# Connectors.net
KiCad netlist of a schematic drawn in Altium Designer
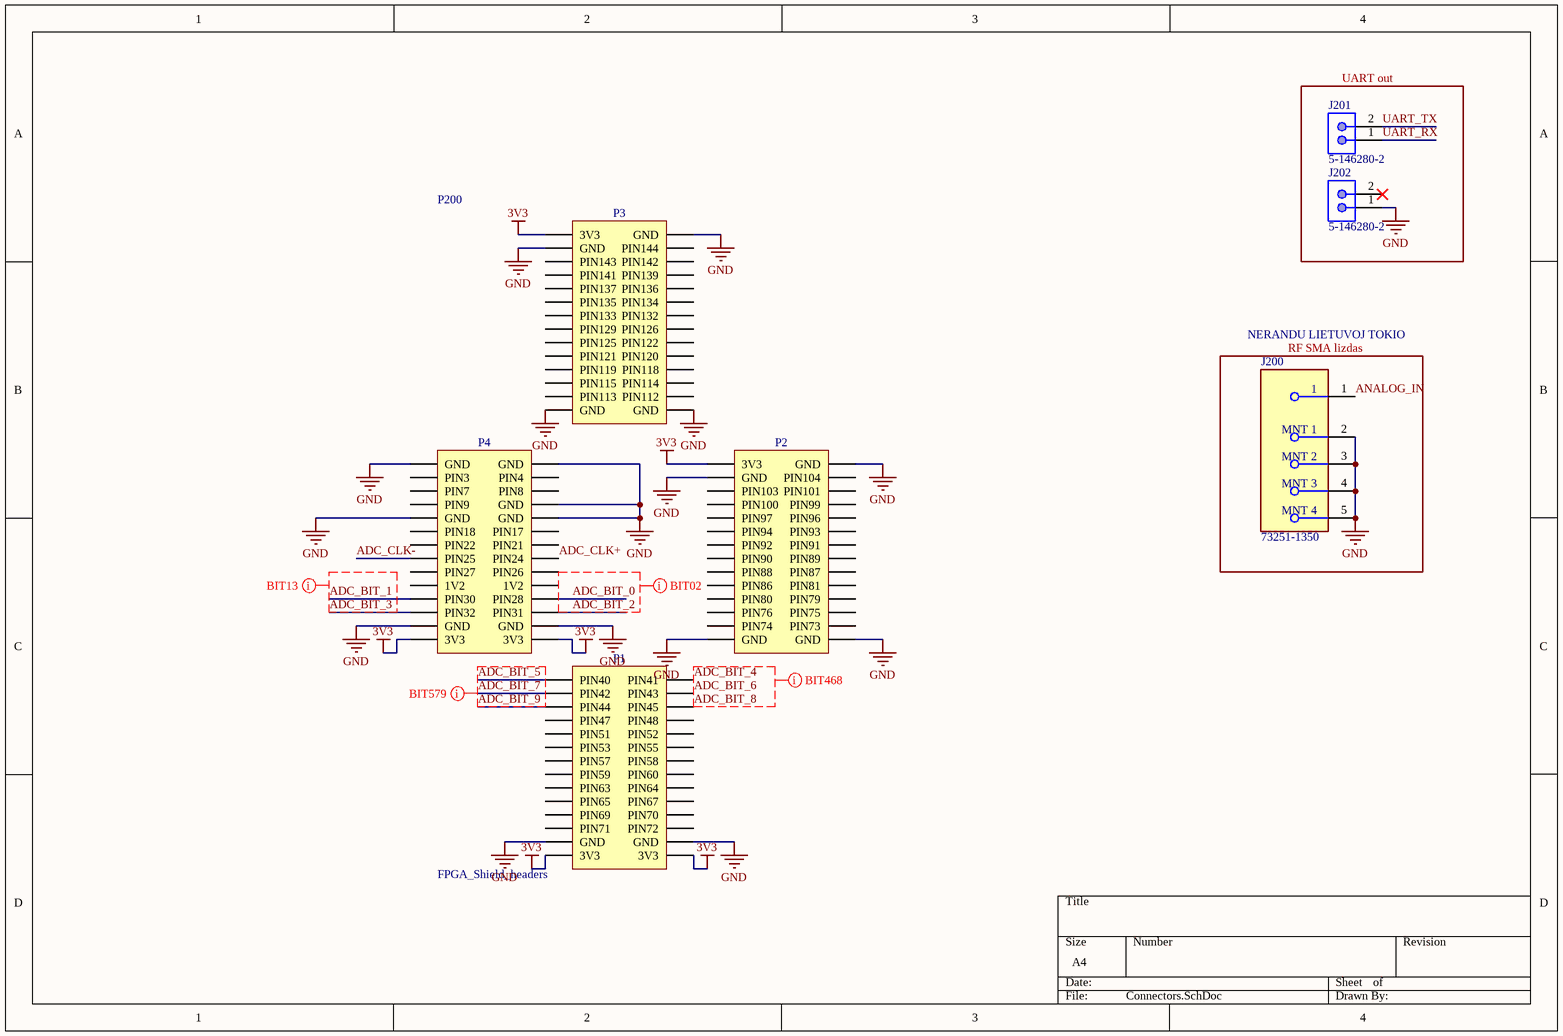
[diagram p0: Connectors.SchDoc]

(export (version "E")
  (design (tool "Eeschema 10.0.6"))
  (components
    (comp (ref "J200")
      (value "73251-1350")
      (footprint "FP-73251-1350-MFG")
      (description "CONN SMA JACK STR 50 OHM SMD")
      (fields
        (field (name "OCTOPART") "https://octopart.com/73251-1350-molex-5414390")
        (field (name "MANUFACTURER") "Molex")
      )
      (libsource (lib "Altium Content Vault") (part "474d33b8a96b1ade9ed6dd87a2b06d4"))
    )
    (comp (ref "J201")
      (value "5-146280-2")
      (footprint "TECO-5-146280-2_V")
      (fields (field (name "MANUFACTURER") "TE Connectivity"))
      (libsource (lib "Altium Content Vault") (part "CN-1P-M-R2"))
    )
    (comp (ref "J202")
      (value "5-146280-2")
      (footprint "TECO-5-146280-2_V")
      (fields (field (name "MANUFACTURER") "TE Connectivity"))
      (libsource (lib "Altium Content Vault") (part "CN-1P-M-R2"))
    )
    (comp (ref "P200")
      (value "FPGA_Shield_headers")
      (footprint "FPGA_SHIELD_HEADER_FOOTPRINT")
      (libsource (lib "Schlib1") (part "FPGA_Shield_headers"))
    )
  )
  (nets
    (net (code "1") (name "/ADC_BIT_0") (class "Default")
      (node (ref "P200") (pin "22") (pinfunction "PIN28_22") (pintype "passive"))
    )
    (net (code "2") (name "/ADC_BIT_1") (class "Default")
      (node (ref "P200") (pin "21") (pinfunction "PIN30_21") (pintype "passive"))
    )
    (net (code "3") (name "/ADC_BIT_2") (class "Default")
      (node (ref "P200") (pin "24") (pinfunction "PIN31_24") (pintype "passive"))
    )
    (net (code "4") (name "/ADC_BIT_3") (class "Default")
      (node (ref "P200") (pin "23") (pinfunction "PIN32_23") (pintype "passive"))
    )
    (net (code "5") (name "/ADC_BIT_4") (class "Default")
      (node (ref "P200") (pin "86") (pinfunction "PIN41_86") (pintype "passive"))
    )
    (net (code "6") (name "/ADC_BIT_5") (class "Default")
      (node (ref "P200") (pin "85") (pinfunction "PIN40_85") (pintype "passive"))
    )
    (net (code "7") (name "/ADC_BIT_6") (class "Default")
      (node (ref "P200") (pin "88") (pinfunction "PIN43_88") (pintype "passive"))
    )
    (net (code "8") (name "/ADC_BIT_7") (class "Default")
      (node (ref "P200") (pin "87") (pinfunction "PIN42_87") (pintype "passive"))
    )
    (net (code "9") (name "/ADC_BIT_8") (class "Default")
      (node (ref "P200") (pin "90") (pinfunction "PIN45_90") (pintype "passive"))
    )
    (net (code "10") (name "/ADC_BIT_9") (class "Default")
      (node (ref "P200") (pin "89") (pinfunction "PIN44_89") (pintype "passive"))
    )
    (net (code "11") (name "/ADC_CLK+") (class "Default")
      (node (ref "P200") (pin "16") (pinfunction "PIN24_16") (pintype "passive"))
    )
    (net (code "12") (name "/ADC_CLK-") (class "Default")
      (node (ref "P200") (pin "15") (pinfunction "PIN25_15") (pintype "passive"))
    )
    (net (code "13") (name "/ANALOG_IN") (class "Default")
      (node (ref "J200") (pin "1") (pinfunction "1_1") (pintype "passive"))
    )
    (net (code "14") (name "/UART_RX") (class "Default")
      (node (ref "J201") (pin "1") (pinfunction "1_1") (pintype "passive"))
    )
    (net (code "15") (name "/UART_TX") (class "Default")
      (node (ref "J201") (pin "2") (pinfunction "2_2") (pintype "passive"))
    )
    (net (code "16") (name "3V3") (class "Default")
      (node (ref "P200") (pin "111") (pinfunction "3V3_111") (pintype "passive"))
      (node (ref "P200") (pin "112") (pinfunction "3V3_112") (pintype "passive"))
      (node (ref "P200") (pin "27") (pinfunction "3V3_27") (pintype "passive"))
      (node (ref "P200") (pin "28") (pinfunction "3V3_28") (pintype "passive"))
      (node (ref "P200") (pin "29") (pinfunction "3V3_29") (pintype "passive"))
      (node (ref "P200") (pin "57") (pinfunction "3V3_57") (pintype "passive"))
    )
    (net (code "17") (name "GND") (class "Default")
      (node (ref "J200") (pin "2") (pinfunction "MNT_1_2") (pintype "passive"))
      (node (ref "J200") (pin "3") (pinfunction "MNT_2_3") (pintype "passive"))
      (node (ref "J200") (pin "4") (pinfunction "MNT_3_4") (pintype "passive"))
      (node (ref "J200") (pin "5") (pinfunction "MNT_4_5") (pintype "passive"))
      (node (ref "J202") (pin "1") (pinfunction "1_1") (pintype "passive"))
      (node (ref "P200") (pin "1") (pinfunction "GND_1") (pintype "passive"))
      (node (ref "P200") (pin "10") (pinfunction "GND_10") (pintype "passive"))
      (node (ref "P200") (pin "109") (pinfunction "GND_109") (pintype "passive"))
      (node (ref "P200") (pin "110") (pinfunction "GND_110") (pintype "passive"))
      (node (ref "P200") (pin "2") (pinfunction "GND_2") (pintype "passive"))
      (node (ref "P200") (pin "25") (pinfunction "GND_25") (pintype "passive"))
      (node (ref "P200") (pin "26") (pinfunction "GND_26") (pintype "passive"))
      (node (ref "P200") (pin "30") (pinfunction "GND_30") (pintype "passive"))
      (node (ref "P200") (pin "31") (pinfunction "GND_31") (pintype "passive"))
      (node (ref "P200") (pin "55") (pinfunction "GND_55") (pintype "passive"))
      (node (ref "P200") (pin "56") (pinfunction "GND_56") (pintype "passive"))
      (node (ref "P200") (pin "58") (pinfunction "GND_58") (pintype "passive"))
      (node (ref "P200") (pin "59") (pinfunction "GND_59") (pintype "passive"))
      (node (ref "P200") (pin "8") (pinfunction "GND_8") (pintype "passive"))
      (node (ref "P200") (pin "83") (pinfunction "GND_83") (pintype "passive"))
      (node (ref "P200") (pin "84") (pinfunction "GND_84") (pintype "passive"))
      (node (ref "P200") (pin "9") (pinfunction "GND_9") (pintype "passive"))
    )
    (net (code "18") (name "unconnected-(J202-Pad2)") (class "Default")
      (node (ref "J202") (pin "2") (pinfunction "2_2") (pintype "passive+no_connect"))
    )
    (net (code "19") (name "unconnected-(P200-1V2-Pad19)") (class "Default")
      (node (ref "P200") (pin "19") (pinfunction "1V2_19") (pintype "passive"))
    )
    (net (code "20") (name "unconnected-(P200-1V2-Pad20)") (class "Default")
      (node (ref "P200") (pin "20") (pinfunction "1V2_20") (pintype "passive"))
    )
    (net (code "21") (name "unconnected-(P200-PIN3-Pad3)") (class "Default")
      (node (ref "P200") (pin "3") (pinfunction "PIN3_3") (pintype "passive"))
    )
    (net (code "22") (name "unconnected-(P200-PIN4-Pad4)") (class "Default")
      (node (ref "P200") (pin "4") (pinfunction "PIN4_4") (pintype "passive"))
    )
    (net (code "23") (name "unconnected-(P200-PIN7-Pad5)") (class "Default")
      (node (ref "P200") (pin "5") (pinfunction "PIN7_5") (pintype "passive"))
    )
    (net (code "24") (name "unconnected-(P200-PIN8-Pad6)") (class "Default")
      (node (ref "P200") (pin "6") (pinfunction "PIN8_6") (pintype "passive"))
    )
    (net (code "25") (name "unconnected-(P200-PIN9-Pad7)") (class "Default")
      (node (ref "P200") (pin "7") (pinfunction "PIN9_7") (pintype "passive"))
    )
    (net (code "26") (name "unconnected-(P200-PIN17-Pad12)") (class "Default")
      (node (ref "P200") (pin "12") (pinfunction "PIN17_12") (pintype "passive"))
    )
    (net (code "27") (name "unconnected-(P200-PIN18-Pad11)") (class "Default")
      (node (ref "P200") (pin "11") (pinfunction "PIN18_11") (pintype "passive"))
    )
    (net (code "28") (name "unconnected-(P200-PIN21-Pad14)") (class "Default")
      (node (ref "P200") (pin "14") (pinfunction "PIN21_14") (pintype "passive"))
    )
    (net (code "29") (name "unconnected-(P200-PIN22-Pad13)") (class "Default")
      (node (ref "P200") (pin "13") (pinfunction "PIN22_13") (pintype "passive"))
    )
    (net (code "30") (name "unconnected-(P200-PIN26-Pad18)") (class "Default")
      (node (ref "P200") (pin "18") (pinfunction "PIN26_18") (pintype "passive"))
    )
    (net (code "31") (name "unconnected-(P200-PIN27-Pad17)") (class "Default")
      (node (ref "P200") (pin "17") (pinfunction "PIN27_17") (pintype "passive"))
    )
    (net (code "32") (name "unconnected-(P200-PIN47-Pad91)") (class "Default")
      (node (ref "P200") (pin "91") (pinfunction "PIN47_91") (pintype "passive"))
    )
    (net (code "33") (name "unconnected-(P200-PIN48-Pad92)") (class "Default")
      (node (ref "P200") (pin "92") (pinfunction "PIN48_92") (pintype "passive"))
    )
    (net (code "34") (name "unconnected-(P200-PIN51-Pad93)") (class "Default")
      (node (ref "P200") (pin "93") (pinfunction "PIN51_93") (pintype "passive"))
    )
    (net (code "35") (name "unconnected-(P200-PIN52-Pad94)") (class "Default")
      (node (ref "P200") (pin "94") (pinfunction "PIN52_94") (pintype "passive"))
    )
    (net (code "36") (name "unconnected-(P200-PIN53-Pad95)") (class "Default")
      (node (ref "P200") (pin "95") (pinfunction "PIN53_95") (pintype "passive"))
    )
    (net (code "37") (name "unconnected-(P200-PIN55-Pad96)") (class "Default")
      (node (ref "P200") (pin "96") (pinfunction "PIN55_96") (pintype "passive"))
    )
    (net (code "38") (name "unconnected-(P200-PIN57-Pad97)") (class "Default")
      (node (ref "P200") (pin "97") (pinfunction "PIN57_97") (pintype "passive"))
    )
    (net (code "39") (name "unconnected-(P200-PIN58-Pad98)") (class "Default")
      (node (ref "P200") (pin "98") (pinfunction "PIN58_98") (pintype "passive"))
    )
    (net (code "40") (name "unconnected-(P200-PIN59-Pad99)") (class "Default")
      (node (ref "P200") (pin "99") (pinfunction "PIN59_99") (pintype "passive"))
    )
    (net (code "41") (name "unconnected-(P200-PIN60-Pad100)") (class "Default")
      (node (ref "P200") (pin "100") (pinfunction "PIN60_100") (pintype "passive"))
    )
    (net (code "42") (name "unconnected-(P200-PIN63-Pad101)") (class "Default")
      (node (ref "P200") (pin "101") (pinfunction "PIN63_101") (pintype "passive"))
    )
    (net (code "43") (name "unconnected-(P200-PIN64-Pad102)") (class "Default")
      (node (ref "P200") (pin "102") (pinfunction "PIN64_102") (pintype "passive"))
    )
    (net (code "44") (name "unconnected-(P200-PIN65-Pad103)") (class "Default")
      (node (ref "P200") (pin "103") (pinfunction "PIN65_103") (pintype "passive"))
    )
    (net (code "45") (name "unconnected-(P200-PIN67-Pad104)") (class "Default")
      (node (ref "P200") (pin "104") (pinfunction "PIN67_104") (pintype "passive"))
    )
    (net (code "46") (name "unconnected-(P200-PIN69-Pad105)") (class "Default")
      (node (ref "P200") (pin "105") (pinfunction "PIN69_105") (pintype "passive"))
    )
    (net (code "47") (name "unconnected-(P200-PIN70-Pad106)") (class "Default")
      (node (ref "P200") (pin "106") (pinfunction "PIN70_106") (pintype "passive"))
    )
    (net (code "48") (name "unconnected-(P200-PIN71-Pad107)") (class "Default")
      (node (ref "P200") (pin "107") (pinfunction "PIN71_107") (pintype "passive"))
    )
    (net (code "49") (name "unconnected-(P200-PIN72-Pad108)") (class "Default")
      (node (ref "P200") (pin "108") (pinfunction "PIN72_108") (pintype "passive"))
    )
    (net (code "50") (name "unconnected-(P200-PIN73-Pad82)") (class "Default")
      (node (ref "P200") (pin "82") (pinfunction "PIN73_82") (pintype "passive"))
    )
    (net (code "51") (name "unconnected-(P200-PIN74-Pad81)") (class "Default")
      (node (ref "P200") (pin "81") (pinfunction "PIN74_81") (pintype "passive"))
    )
    (net (code "52") (name "unconnected-(P200-PIN75-Pad80)") (class "Default")
      (node (ref "P200") (pin "80") (pinfunction "PIN75_80") (pintype "passive"))
    )
    (net (code "53") (name "unconnected-(P200-PIN76-Pad79)") (class "Default")
      (node (ref "P200") (pin "79") (pinfunction "PIN76_79") (pintype "passive"))
    )
    (net (code "54") (name "unconnected-(P200-PIN79-Pad78)") (class "Default")
      (node (ref "P200") (pin "78") (pinfunction "PIN79_78") (pintype "passive"))
    )
    (net (code "55") (name "unconnected-(P200-PIN80-Pad77)") (class "Default")
      (node (ref "P200") (pin "77") (pinfunction "PIN80_77") (pintype "passive"))
    )
    (net (code "56") (name "unconnected-(P200-PIN81-Pad76)") (class "Default")
      (node (ref "P200") (pin "76") (pinfunction "PIN81_76") (pintype "passive"))
    )
    (net (code "57") (name "unconnected-(P200-PIN86-Pad75)") (class "Default")
      (node (ref "P200") (pin "75") (pinfunction "PIN86_75") (pintype "passive"))
    )
    (net (code "58") (name "unconnected-(P200-PIN87-Pad74)") (class "Default")
      (node (ref "P200") (pin "74") (pinfunction "PIN87_74") (pintype "passive"))
    )
    (net (code "59") (name "unconnected-(P200-PIN88-Pad73)") (class "Default")
      (node (ref "P200") (pin "73") (pinfunction "PIN88_73") (pintype "passive"))
    )
    (net (code "60") (name "unconnected-(P200-PIN89-Pad72)") (class "Default")
      (node (ref "P200") (pin "72") (pinfunction "PIN89_72") (pintype "passive"))
    )
    (net (code "61") (name "unconnected-(P200-PIN90-Pad71)") (class "Default")
      (node (ref "P200") (pin "71") (pinfunction "PIN90_71") (pintype "passive"))
    )
    (net (code "62") (name "unconnected-(P200-PIN91-Pad70)") (class "Default")
      (node (ref "P200") (pin "70") (pinfunction "PIN91_70") (pintype "passive"))
    )
    (net (code "63") (name "unconnected-(P200-PIN92-Pad69)") (class "Default")
      (node (ref "P200") (pin "69") (pinfunction "PIN92_69") (pintype "passive"))
    )
    (net (code "64") (name "unconnected-(P200-PIN93-Pad68)") (class "Default")
      (node (ref "P200") (pin "68") (pinfunction "PIN93_68") (pintype "passive"))
    )
    (net (code "65") (name "unconnected-(P200-PIN94-Pad67)") (class "Default")
      (node (ref "P200") (pin "67") (pinfunction "PIN94_67") (pintype "passive"))
    )
    (net (code "66") (name "unconnected-(P200-PIN96-Pad66)") (class "Default")
      (node (ref "P200") (pin "66") (pinfunction "PIN96_66") (pintype "passive"))
    )
    (net (code "67") (name "unconnected-(P200-PIN97-Pad65)") (class "Default")
      (node (ref "P200") (pin "65") (pinfunction "PIN97_65") (pintype "passive"))
    )
    (net (code "68") (name "unconnected-(P200-PIN99-Pad64)") (class "Default")
      (node (ref "P200") (pin "64") (pinfunction "PIN99_64") (pintype "passive"))
    )
    (net (code "69") (name "unconnected-(P200-PIN100-Pad63)") (class "Default")
      (node (ref "P200") (pin "63") (pinfunction "PIN100_63") (pintype "passive"))
    )
    (net (code "70") (name "unconnected-(P200-PIN101-Pad62)") (class "Default")
      (node (ref "P200") (pin "62") (pinfunction "PIN101_62") (pintype "passive"))
    )
    (net (code "71") (name "unconnected-(P200-PIN103-Pad61)") (class "Default")
      (node (ref "P200") (pin "61") (pinfunction "PIN103_61") (pintype "passive"))
    )
    (net (code "72") (name "unconnected-(P200-PIN104-Pad60)") (class "Default")
      (node (ref "P200") (pin "60") (pinfunction "PIN104_60") (pintype "passive"))
    )
    (net (code "73") (name "unconnected-(P200-PIN112-Pad54)") (class "Default")
      (node (ref "P200") (pin "54") (pinfunction "PIN112_54") (pintype "passive"))
    )
    (net (code "74") (name "unconnected-(P200-PIN113-Pad53)") (class "Default")
      (node (ref "P200") (pin "53") (pinfunction "PIN113_53") (pintype "passive"))
    )
    (net (code "75") (name "unconnected-(P200-PIN114-Pad52)") (class "Default")
      (node (ref "P200") (pin "52") (pinfunction "PIN114_52") (pintype "passive"))
    )
    (net (code "76") (name "unconnected-(P200-PIN115-Pad51)") (class "Default")
      (node (ref "P200") (pin "51") (pinfunction "PIN115_51") (pintype "passive"))
    )
    (net (code "77") (name "unconnected-(P200-PIN118-Pad50)") (class "Default")
      (node (ref "P200") (pin "50") (pinfunction "PIN118_50") (pintype "passive"))
    )
    (net (code "78") (name "unconnected-(P200-PIN119-Pad49)") (class "Default")
      (node (ref "P200") (pin "49") (pinfunction "PIN119_49") (pintype "passive"))
    )
    (net (code "79") (name "unconnected-(P200-PIN120-Pad48)") (class "Default")
      (node (ref "P200") (pin "48") (pinfunction "PIN120_48") (pintype "passive"))
    )
    (net (code "80") (name "unconnected-(P200-PIN121-Pad47)") (class "Default")
      (node (ref "P200") (pin "47") (pinfunction "PIN121_47") (pintype "passive"))
    )
    (net (code "81") (name "unconnected-(P200-PIN122-Pad46)") (class "Default")
      (node (ref "P200") (pin "46") (pinfunction "PIN122_46") (pintype "passive"))
    )
    (net (code "82") (name "unconnected-(P200-PIN125-Pad45)") (class "Default")
      (node (ref "P200") (pin "45") (pinfunction "PIN125_45") (pintype "passive"))
    )
    (net (code "83") (name "unconnected-(P200-PIN126-Pad44)") (class "Default")
      (node (ref "P200") (pin "44") (pinfunction "PIN126_44") (pintype "passive"))
    )
    (net (code "84") (name "unconnected-(P200-PIN129-Pad43)") (class "Default")
      (node (ref "P200") (pin "43") (pinfunction "PIN129_43") (pintype "passive"))
    )
    (net (code "85") (name "unconnected-(P200-PIN132-Pad42)") (class "Default")
      (node (ref "P200") (pin "42") (pinfunction "PIN132_42") (pintype "passive"))
    )
    (net (code "86") (name "unconnected-(P200-PIN133-Pad41)") (class "Default")
      (node (ref "P200") (pin "41") (pinfunction "PIN133_41") (pintype "passive"))
    )
    (net (code "87") (name "unconnected-(P200-PIN134-Pad40)") (class "Default")
      (node (ref "P200") (pin "40") (pinfunction "PIN134_40") (pintype "passive"))
    )
    (net (code "88") (name "unconnected-(P200-PIN135-Pad39)") (class "Default")
      (node (ref "P200") (pin "39") (pinfunction "PIN135_39") (pintype "passive"))
    )
    (net (code "89") (name "unconnected-(P200-PIN136-Pad38)") (class "Default")
      (node (ref "P200") (pin "38") (pinfunction "PIN136_38") (pintype "passive"))
    )
    (net (code "90") (name "unconnected-(P200-PIN137-Pad37)") (class "Default")
      (node (ref "P200") (pin "37") (pinfunction "PIN137_37") (pintype "passive"))
    )
    (net (code "91") (name "unconnected-(P200-PIN139-Pad36)") (class "Default")
      (node (ref "P200") (pin "36") (pinfunction "PIN139_36") (pintype "passive"))
    )
    (net (code "92") (name "unconnected-(P200-PIN141-Pad35)") (class "Default")
      (node (ref "P200") (pin "35") (pinfunction "PIN141_35") (pintype "passive"))
    )
    (net (code "93") (name "unconnected-(P200-PIN142-Pad34)") (class "Default")
      (node (ref "P200") (pin "34") (pinfunction "PIN142_34") (pintype "passive"))
    )
    (net (code "94") (name "unconnected-(P200-PIN143-Pad33)") (class "Default")
      (node (ref "P200") (pin "33") (pinfunction "PIN143_33") (pintype "passive"))
    )
    (net (code "95") (name "unconnected-(P200-PIN144-Pad32)") (class "Default")
      (node (ref "P200") (pin "32") (pinfunction "PIN144_32") (pintype "passive"))
    )
  )
)
